# precharge.net
KiCad netlist of a schematic drawn in EAGLE
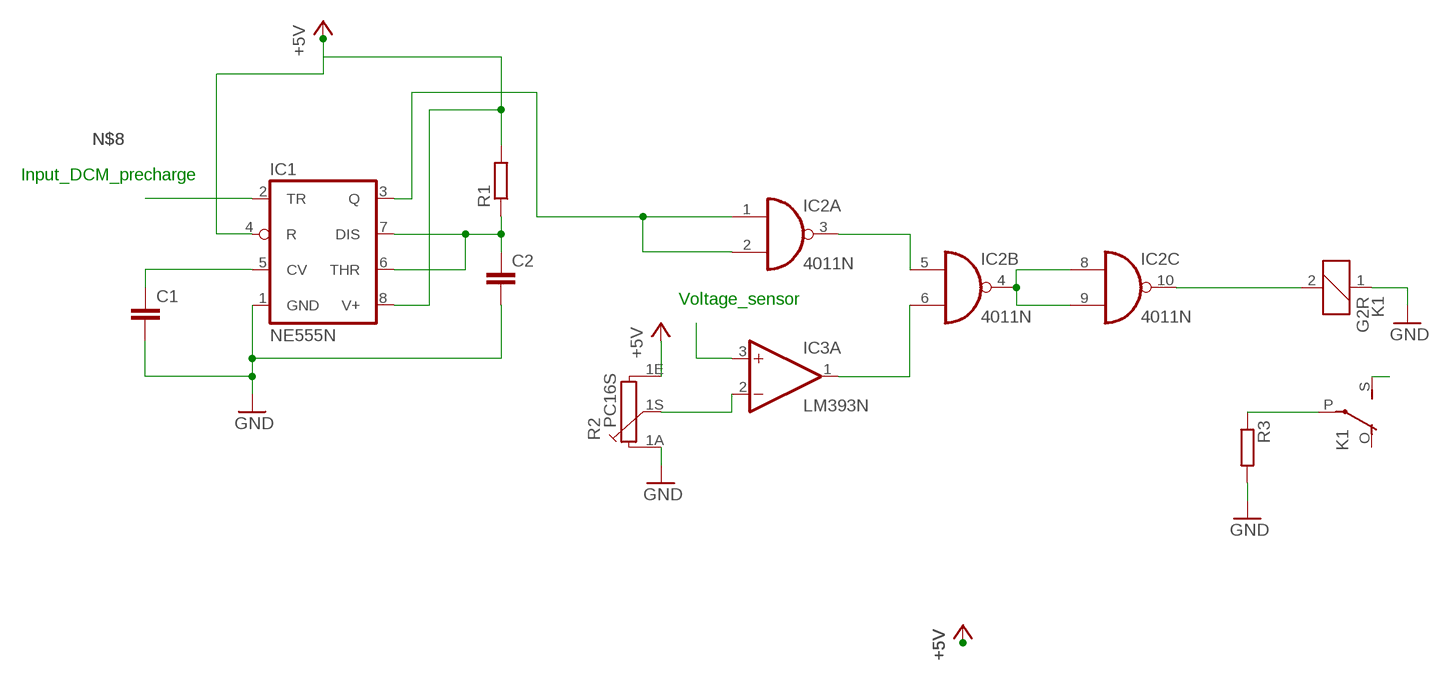
[diagram p0: schematic, sheet 1]

(export (version "E")
  (design (tool "Eeschema 10.0.6"))
  (components
    (comp (ref "C1")
      (value "C5/3")
      (footprint "eagle-import:C5B3")
      (libsource (lib "eagle-import") (part "C5/3"))
    )
    (comp (ref "C2")
      (value "C7.5/3")
      (footprint "eagle-import:C7.5B3")
      (libsource (lib "eagle-import") (part "C7.5/3"))
    )
    (comp (ref "IC1")
      (value "NE555N")
      (footprint "eagle-import:DIL08")
      (libsource (lib "eagle-import") (part "555NNE"))
    )
    (comp (ref "IC2")
      (value "4011N")
      (footprint "eagle-import:DIL14")
      (libsource (lib "eagle-import") (part "4011N"))
    )
    (comp (ref "IC3")
      (value "LM393N")
      (footprint "eagle-import:DIL08")
      (libsource (lib "eagle-import") (part "LM393N"))
    )
    (comp (ref "K1")
      (value "G2R")
      (footprint "eagle-import:G2R")
      (libsource (lib "eagle-import") (part "G2R"))
    )
    (comp (ref "R1")
      (value "R-EU_0204/7")
      (footprint "eagle-import:0204_7")
      (libsource (lib "eagle-import") (part "R-EU_0204/7"))
    )
    (comp (ref "R2")
      (value "PC16S")
      (footprint "eagle-import:PC16S")
      (libsource (lib "eagle-import") (part "PC16S"))
    )
    (comp (ref "R3")
      (value "R-EU_0207/10")
      (footprint "eagle-import:0207_10")
      (libsource (lib "eagle-import") (part "R-EU_0207/10"))
    )
  )
  (nets
    (net (code "1") (name "+5V") (class "Default")
      (node (ref "IC1") (pin "4") (pinfunction "R_4") (pintype "input"))
      (node (ref "IC1") (pin "8") (pinfunction "V+_8") (pintype "power_in"))
      (node (ref "R1") (pin "2") (pinfunction "2_2") (pintype "passive"))
      (node (ref "R2") (pin "1E") (pinfunction "1E_1E") (pintype "passive"))
    )
    (net (code "2") (name "/N$8") (class "Default")
      (node (ref "IC1") (pin "2") (pinfunction "TR_2") (pintype "input"))
    )
    (net (code "3") (name "GND") (class "Default")
      (node (ref "C1") (pin "2") (pinfunction "2_2") (pintype "passive"))
      (node (ref "C2") (pin "2") (pinfunction "2_2") (pintype "passive"))
      (node (ref "IC1") (pin "1") (pinfunction "GND_1") (pintype "power_in"))
      (node (ref "K1") (pin "1") (pinfunction "1_1") (pintype "passive"))
      (node (ref "R2") (pin "1A") (pinfunction "1A_1A") (pintype "passive"))
      (node (ref "R3") (pin "2") (pinfunction "2_2") (pintype "passive"))
    )
    (net (code "4") (name "Net-(IC1-CV)") (class "Default")
      (node (ref "C1") (pin "1") (pinfunction "1_1") (pintype "passive"))
      (node (ref "IC1") (pin "5") (pinfunction "CV_5") (pintype "input"))
    )
    (net (code "5") (name "Net-(IC1-DIS)") (class "Default")
      (node (ref "C2") (pin "1") (pinfunction "1_1") (pintype "passive"))
      (node (ref "IC1") (pin "6") (pinfunction "THR_6") (pintype "input"))
      (node (ref "IC1") (pin "7") (pinfunction "DIS_7") (pintype "input"))
      (node (ref "R1") (pin "1") (pinfunction "1_1") (pintype "passive"))
    )
    (net (code "6") (name "Net-(IC1-Q)") (class "Default")
      (node (ref "IC1") (pin "3") (pinfunction "Q_3") (pintype "output"))
      (node (ref "IC2") (pin "1") (pinfunction "I0_1") (pintype "input"))
      (node (ref "IC2") (pin "2") (pinfunction "I1_2") (pintype "input"))
    )
    (net (code "7") (name "Net-(IC2A-O)") (class "Default")
      (node (ref "IC2") (pin "3") (pinfunction "O_3") (pintype "output"))
      (node (ref "IC2") (pin "5") (pinfunction "I0_5") (pintype "input"))
    )
    (net (code "8") (name "Net-(IC2B-I1)") (class "Default")
      (node (ref "IC2") (pin "6") (pinfunction "I1_6") (pintype "input"))
      (node (ref "IC3") (pin "1") (pinfunction "OUT_1") (pintype "output"))
    )
    (net (code "9") (name "Net-(IC2B-O)") (class "Default")
      (node (ref "IC2") (pin "4") (pinfunction "O_4") (pintype "output"))
      (node (ref "IC2") (pin "8") (pinfunction "I0_8") (pintype "input"))
      (node (ref "IC2") (pin "9") (pinfunction "I1_9") (pintype "input"))
    )
    (net (code "10") (name "Net-(IC2C-O)") (class "Default")
      (node (ref "IC2") (pin "10") (pinfunction "O_10") (pintype "output"))
      (node (ref "K1") (pin "2") (pinfunction "2_2") (pintype "passive"))
    )
    (net (code "11") (name "Net-(IC3A--IN)") (class "Default")
      (node (ref "IC3") (pin "2") (pinfunction "-IN_2") (pintype "input"))
      (node (ref "R2") (pin "1S") (pinfunction "1S_1S") (pintype "passive"))
    )
    (net (code "12") (name "Net-(K1-PadP)") (class "Default")
      (node (ref "K1") (pin "P") (pinfunction "P_P") (pintype "passive"))
      (node (ref "R3") (pin "1") (pinfunction "1_1") (pintype "passive"))
    )
    (net (code "13") (name "unconnected-(IC3A-+IN-Pad3)") (class "Default")
      (node (ref "IC3") (pin "3") (pinfunction "+IN_3") (pintype "input"))
    )
    (net (code "14") (name "unconnected-(K1-PadO)") (class "Default")
      (node (ref "K1") (pin "O") (pinfunction "O_O") (pintype "passive"))
    )
    (net (code "15") (name "unconnected-(K1-PadS)") (class "Default")
      (node (ref "K1") (pin "S") (pinfunction "S_S") (pintype "passive"))
    )
  )
)
